# Sch.net
KiCad netlist of a schematic drawn in Altium Designer
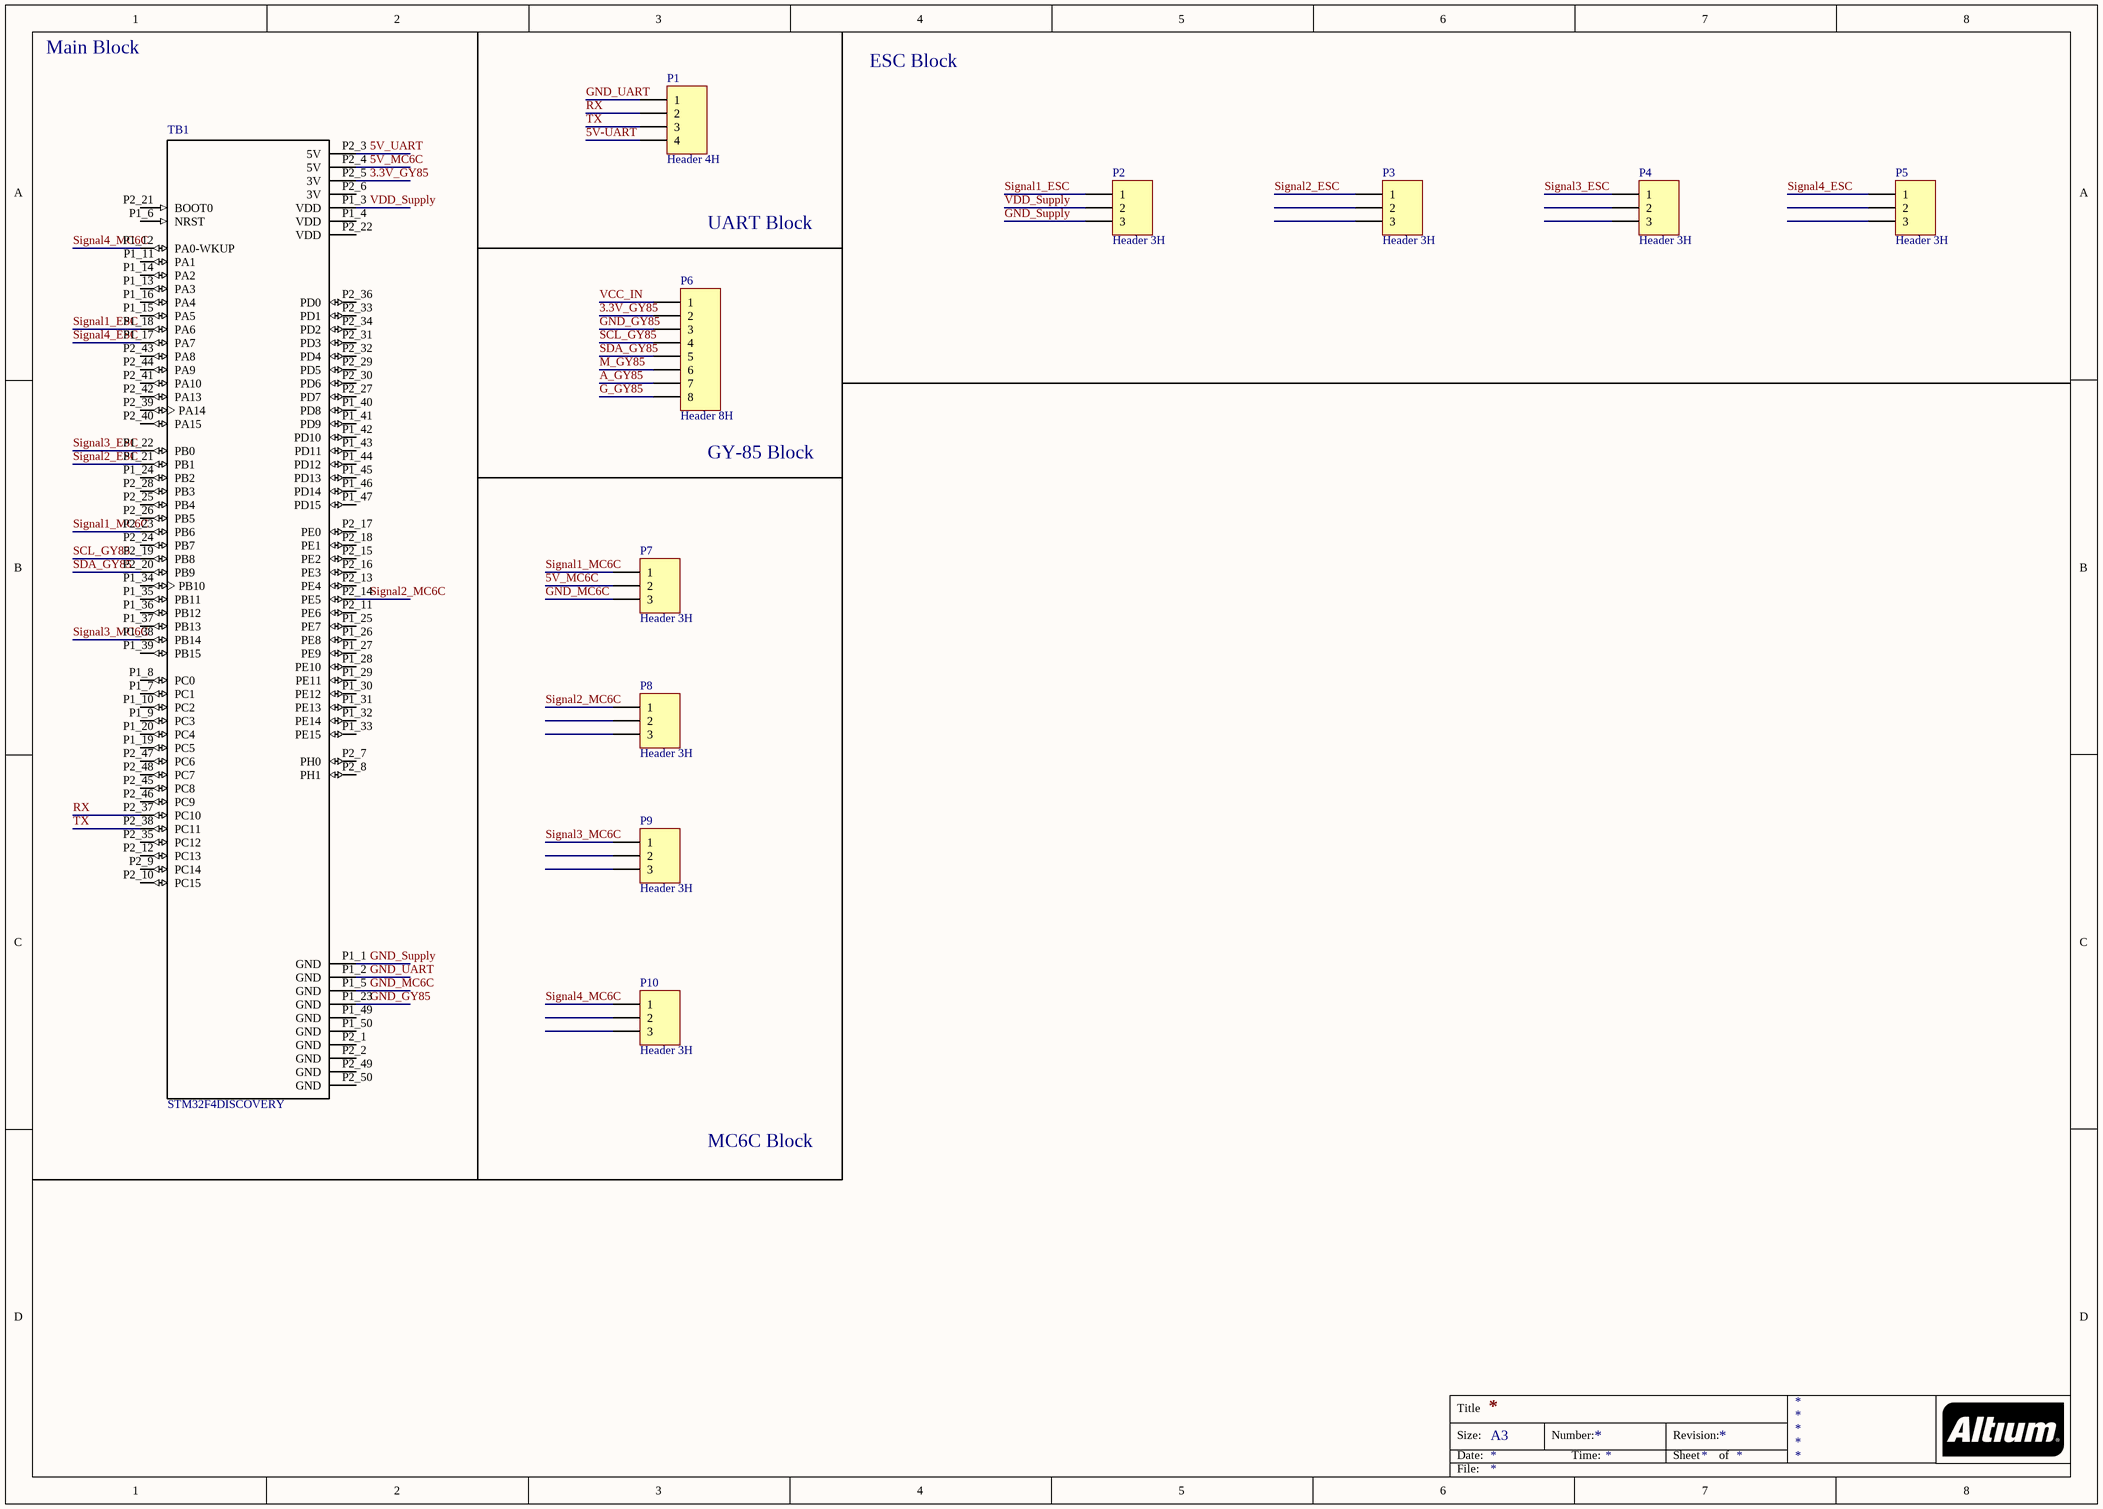
[diagram p0: Sch.SchDoc]

(export (version "E")
  (design (tool "Eeschema 10.0.6"))
  (components
    (comp (ref "P1")
      (value "Header 4H")
      (footprint "HDR1X4H")
      (description "Header, 4-Pin, Right Angle")
      (fields (field (name "PUBLISHER") "Altium Limited"))
      (libsource (lib "Miscellaneous Connectors") (part "Header 4H"))
    )
    (comp (ref "P2")
      (value "Header 3H")
      (footprint "HDR1X3H")
      (description "Header, 3-Pin, Right Angle")
      (fields (field (name "PUBLISHER") "Altium Limited"))
      (libsource (lib "Miscellaneous Connectors") (part "Header 3H"))
    )
    (comp (ref "P3")
      (value "Header 3H")
      (footprint "HDR1X3H")
      (description "Header, 3-Pin, Right Angle")
      (fields (field (name "PUBLISHER") "Altium Limited"))
      (libsource (lib "Miscellaneous Connectors") (part "Header 3H"))
    )
    (comp (ref "P4")
      (value "Header 3H")
      (footprint "HDR1X3H")
      (description "Header, 3-Pin, Right Angle")
      (fields (field (name "PUBLISHER") "Altium Limited"))
      (libsource (lib "Miscellaneous Connectors") (part "Header 3H"))
    )
    (comp (ref "P5")
      (value "Header 3H")
      (footprint "HDR1X3H")
      (description "Header, 3-Pin, Right Angle")
      (fields (field (name "PUBLISHER") "Altium Limited"))
      (libsource (lib "Miscellaneous Connectors") (part "Header 3H"))
    )
    (comp (ref "P6")
      (value "Header 8H")
      (footprint "HDR1X8H")
      (description "Header, 8-Pin, Right Angle")
      (fields (field (name "PUBLISHER") "Altium Limited"))
      (libsource (lib "Miscellaneous Connectors") (part "Header 8H"))
    )
    (comp (ref "P7")
      (value "Header 3H")
      (footprint "HDR1X3H")
      (description "Header, 3-Pin, Right Angle")
      (fields (field (name "PUBLISHER") "Altium Limited"))
      (libsource (lib "Miscellaneous Connectors") (part "Header 3H"))
    )
    (comp (ref "P8")
      (value "Header 3H")
      (footprint "HDR1X3H")
      (description "Header, 3-Pin, Right Angle")
      (fields (field (name "PUBLISHER") "Altium Limited"))
      (libsource (lib "Miscellaneous Connectors") (part "Header 3H"))
    )
    (comp (ref "P9")
      (value "Header 3H")
      (footprint "HDR1X3H")
      (description "Header, 3-Pin, Right Angle")
      (fields (field (name "PUBLISHER") "Altium Limited"))
      (libsource (lib "Miscellaneous Connectors") (part "Header 3H"))
    )
    (comp (ref "P10")
      (value "Header 3H")
      (footprint "HDR1X3H")
      (description "Header, 3-Pin, Right Angle")
      (fields (field (name "PUBLISHER") "Altium Limited"))
      (libsource (lib "Miscellaneous Connectors") (part "Header 3H"))
    )
    (comp (ref "TB1")
      (value "STM32F4DISCOVERY")
      (footprint "*MODULE_STM32F4DISCOVERY_STM32F4DISCOVERY(Primary)")
      (description "STM32F407VGT6 Discovery STM32F4 ARMÂ® CortexÂ®-M4 MCU 32-Bit Embedded Evaluation Board")
      (fields (field (name "MF") "STMicroelectronics"))
      (libsource (lib "STM32F4DISCOVERY") (part "STM32F4DISCOVERY"))
    )
  )
  (nets
    (net (code "1") (name "/3.3V_GY85") (class "Default")
      (node (ref "P6") (pin "2") (pinfunction "2_2") (pintype "passive"))
      (node (ref "TB1") (pin "P2_5") (pinfunction "3V_P2_5") (pintype "power_in"))
    )
    (net (code "2") (name "/5V-UART") (class "Default")
      (node (ref "P1") (pin "4") (pinfunction "4_4") (pintype "passive"))
    )
    (net (code "3") (name "/5V_MC6C") (class "Default")
      (node (ref "P7") (pin "2") (pinfunction "2_2") (pintype "passive"))
      (node (ref "TB1") (pin "P2_4") (pinfunction "5V_P2_4") (pintype "power_in"))
    )
    (net (code "4") (name "/5V_UART") (class "Default")
      (node (ref "TB1") (pin "P2_3") (pinfunction "5V_P2_3") (pintype "power_in"))
    )
    (net (code "5") (name "/A_GY85") (class "Default")
      (node (ref "P6") (pin "7") (pinfunction "7_7") (pintype "passive"))
    )
    (net (code "6") (name "/GND_GY85") (class "Default")
      (node (ref "P6") (pin "3") (pinfunction "3_3") (pintype "passive"))
      (node (ref "TB1") (pin "P1_23") (pinfunction "GND_P1_23") (pintype "power_in"))
    )
    (net (code "7") (name "/GND_MC6C") (class "Default")
      (node (ref "P7") (pin "3") (pinfunction "3_3") (pintype "passive"))
      (node (ref "TB1") (pin "P1_5") (pinfunction "GND_P1_5") (pintype "power_in"))
    )
    (net (code "8") (name "/GND_Supply") (class "Default")
      (node (ref "P2") (pin "3") (pinfunction "3_3") (pintype "passive"))
      (node (ref "TB1") (pin "P1_1") (pinfunction "GND_P1_1") (pintype "power_in"))
    )
    (net (code "9") (name "/GND_UART") (class "Default")
      (node (ref "P1") (pin "1") (pinfunction "1_1") (pintype "passive"))
      (node (ref "TB1") (pin "P1_2") (pinfunction "GND_P1_2") (pintype "power_in"))
    )
    (net (code "10") (name "/G_GY85") (class "Default")
      (node (ref "P6") (pin "8") (pinfunction "8_8") (pintype "passive"))
    )
    (net (code "11") (name "/M_GY85") (class "Default")
      (node (ref "P6") (pin "6") (pinfunction "6_6") (pintype "passive"))
    )
    (net (code "12") (name "/RX") (class "Default")
      (node (ref "P1") (pin "2") (pinfunction "2_2") (pintype "passive"))
      (node (ref "TB1") (pin "P2_37") (pinfunction "PC10_P2_37") (pintype "bidirectional"))
    )
    (net (code "13") (name "/SCL_GY85") (class "Default")
      (node (ref "P6") (pin "4") (pinfunction "4_4") (pintype "passive"))
      (node (ref "TB1") (pin "P2_19") (pinfunction "PB8_P2_19") (pintype "bidirectional"))
    )
    (net (code "14") (name "/SDA_GY85") (class "Default")
      (node (ref "P6") (pin "5") (pinfunction "5_5") (pintype "passive"))
      (node (ref "TB1") (pin "P2_20") (pinfunction "PB9_P2_20") (pintype "bidirectional"))
    )
    (net (code "15") (name "/Signal1_ESC") (class "Default")
      (node (ref "P2") (pin "1") (pinfunction "1_1") (pintype "passive"))
      (node (ref "TB1") (pin "P1_18") (pinfunction "PA6_P1_18") (pintype "bidirectional"))
    )
    (net (code "16") (name "/Signal1_MC6C") (class "Default")
      (node (ref "P7") (pin "1") (pinfunction "1_1") (pintype "passive"))
      (node (ref "TB1") (pin "P2_23") (pinfunction "PB6_P2_23") (pintype "bidirectional"))
    )
    (net (code "17") (name "/Signal2_ESC") (class "Default")
      (node (ref "P3") (pin "1") (pinfunction "1_1") (pintype "passive"))
      (node (ref "TB1") (pin "P1_21") (pinfunction "PB1_P1_21") (pintype "bidirectional"))
    )
    (net (code "18") (name "/Signal2_MC6C") (class "Default")
      (node (ref "P8") (pin "1") (pinfunction "1_1") (pintype "passive"))
      (node (ref "TB1") (pin "P2_14") (pinfunction "PE5_P2_14") (pintype "bidirectional"))
    )
    (net (code "19") (name "/Signal3_ESC") (class "Default")
      (node (ref "P4") (pin "1") (pinfunction "1_1") (pintype "passive"))
      (node (ref "TB1") (pin "P1_22") (pinfunction "PB0_P1_22") (pintype "bidirectional"))
    )
    (net (code "20") (name "/Signal3_MC6C") (class "Default")
      (node (ref "P9") (pin "1") (pinfunction "1_1") (pintype "passive"))
      (node (ref "TB1") (pin "P1_38") (pinfunction "PB14_P1_38") (pintype "bidirectional"))
    )
    (net (code "21") (name "/Signal4_ESC") (class "Default")
      (node (ref "P5") (pin "1") (pinfunction "1_1") (pintype "passive"))
      (node (ref "TB1") (pin "P1_17") (pinfunction "PA7_P1_17") (pintype "bidirectional"))
    )
    (net (code "22") (name "/Signal4_MC6C") (class "Default")
      (node (ref "P10") (pin "1") (pinfunction "1_1") (pintype "passive"))
      (node (ref "TB1") (pin "P1_12") (pinfunction "PA0-WKUP_P1_12") (pintype "bidirectional"))
    )
    (net (code "23") (name "/TX") (class "Default")
      (node (ref "P1") (pin "3") (pinfunction "3_3") (pintype "passive"))
      (node (ref "TB1") (pin "P2_38") (pinfunction "PC11_P2_38") (pintype "bidirectional"))
    )
    (net (code "24") (name "/VCC_IN") (class "Default")
      (node (ref "P6") (pin "1") (pinfunction "1_1") (pintype "passive"))
    )
    (net (code "25") (name "/VDD_Supply") (class "Default")
      (node (ref "P2") (pin "2") (pinfunction "2_2") (pintype "passive"))
      (node (ref "TB1") (pin "P1_3") (pinfunction "VDD_P1_3") (pintype "power_in"))
    )
    (net (code "26") (name "unconnected-(P3-Pad2)") (class "Default")
      (node (ref "P3") (pin "2") (pinfunction "2_2") (pintype "passive"))
    )
    (net (code "27") (name "unconnected-(P3-Pad3)") (class "Default")
      (node (ref "P3") (pin "3") (pinfunction "3_3") (pintype "passive"))
    )
    (net (code "28") (name "unconnected-(P4-Pad2)") (class "Default")
      (node (ref "P4") (pin "2") (pinfunction "2_2") (pintype "passive"))
    )
    (net (code "29") (name "unconnected-(P4-Pad3)") (class "Default")
      (node (ref "P4") (pin "3") (pinfunction "3_3") (pintype "passive"))
    )
    (net (code "30") (name "unconnected-(P5-Pad2)") (class "Default")
      (node (ref "P5") (pin "2") (pinfunction "2_2") (pintype "passive"))
    )
    (net (code "31") (name "unconnected-(P5-Pad3)") (class "Default")
      (node (ref "P5") (pin "3") (pinfunction "3_3") (pintype "passive"))
    )
    (net (code "32") (name "unconnected-(P8-Pad2)") (class "Default")
      (node (ref "P8") (pin "2") (pinfunction "2_2") (pintype "passive"))
    )
    (net (code "33") (name "unconnected-(P8-Pad3)") (class "Default")
      (node (ref "P8") (pin "3") (pinfunction "3_3") (pintype "passive"))
    )
    (net (code "34") (name "unconnected-(P9-Pad2)") (class "Default")
      (node (ref "P9") (pin "2") (pinfunction "2_2") (pintype "passive"))
    )
    (net (code "35") (name "unconnected-(P9-Pad3)") (class "Default")
      (node (ref "P9") (pin "3") (pinfunction "3_3") (pintype "passive"))
    )
    (net (code "36") (name "unconnected-(P10-Pad2)") (class "Default")
      (node (ref "P10") (pin "2") (pinfunction "2_2") (pintype "passive"))
    )
    (net (code "37") (name "unconnected-(P10-Pad3)") (class "Default")
      (node (ref "P10") (pin "3") (pinfunction "3_3") (pintype "passive"))
    )
    (net (code "38") (name "unconnected-(TB1-3V-PadP2_6)") (class "Default")
      (node (ref "TB1") (pin "P2_6") (pinfunction "3V_P2_6") (pintype "power_in"))
    )
    (net (code "39") (name "unconnected-(TB1-BOOT0-PadP2_21)") (class "Default")
      (node (ref "TB1") (pin "P2_21") (pinfunction "BOOT0_P2_21") (pintype "input"))
    )
    (net (code "40") (name "unconnected-(TB1-GND-PadP1_49)") (class "Default")
      (node (ref "TB1") (pin "P1_49") (pinfunction "GND_P1_49") (pintype "power_in"))
    )
    (net (code "41") (name "unconnected-(TB1-GND-PadP1_50)") (class "Default")
      (node (ref "TB1") (pin "P1_50") (pinfunction "GND_P1_50") (pintype "power_in"))
    )
    (net (code "42") (name "unconnected-(TB1-GND-PadP2_1)") (class "Default")
      (node (ref "TB1") (pin "P2_1") (pinfunction "GND_P2_1") (pintype "power_in"))
    )
    (net (code "43") (name "unconnected-(TB1-GND-PadP2_2)") (class "Default")
      (node (ref "TB1") (pin "P2_2") (pinfunction "GND_P2_2") (pintype "power_in"))
    )
    (net (code "44") (name "unconnected-(TB1-GND-PadP2_49)") (class "Default")
      (node (ref "TB1") (pin "P2_49") (pinfunction "GND_P2_49") (pintype "power_in"))
    )
    (net (code "45") (name "unconnected-(TB1-GND-PadP2_50)") (class "Default")
      (node (ref "TB1") (pin "P2_50") (pinfunction "GND_P2_50") (pintype "power_in"))
    )
    (net (code "46") (name "unconnected-(TB1-NRST-PadP1_6)") (class "Default")
      (node (ref "TB1") (pin "P1_6") (pinfunction "NRST_P1_6") (pintype "input"))
    )
    (net (code "47") (name "unconnected-(TB1-PA1-PadP1_11)") (class "Default")
      (node (ref "TB1") (pin "P1_11") (pinfunction "PA1_P1_11") (pintype "bidirectional"))
    )
    (net (code "48") (name "unconnected-(TB1-PA2-PadP1_14)") (class "Default")
      (node (ref "TB1") (pin "P1_14") (pinfunction "PA2_P1_14") (pintype "bidirectional"))
    )
    (net (code "49") (name "unconnected-(TB1-PA3-PadP1_13)") (class "Default")
      (node (ref "TB1") (pin "P1_13") (pinfunction "PA3_P1_13") (pintype "bidirectional"))
    )
    (net (code "50") (name "unconnected-(TB1-PA4-PadP1_16)") (class "Default")
      (node (ref "TB1") (pin "P1_16") (pinfunction "PA4_P1_16") (pintype "bidirectional"))
    )
    (net (code "51") (name "unconnected-(TB1-PA5-PadP1_15)") (class "Default")
      (node (ref "TB1") (pin "P1_15") (pinfunction "PA5_P1_15") (pintype "bidirectional"))
    )
    (net (code "52") (name "unconnected-(TB1-PA8-PadP2_43)") (class "Default")
      (node (ref "TB1") (pin "P2_43") (pinfunction "PA8_P2_43") (pintype "bidirectional"))
    )
    (net (code "53") (name "unconnected-(TB1-PA9-PadP2_44)") (class "Default")
      (node (ref "TB1") (pin "P2_44") (pinfunction "PA9_P2_44") (pintype "bidirectional"))
    )
    (net (code "54") (name "unconnected-(TB1-PA10-PadP2_41)") (class "Default")
      (node (ref "TB1") (pin "P2_41") (pinfunction "PA10_P2_41") (pintype "bidirectional"))
    )
    (net (code "55") (name "unconnected-(TB1-PA13-PadP2_42)") (class "Default")
      (node (ref "TB1") (pin "P2_42") (pinfunction "PA13_P2_42") (pintype "bidirectional"))
    )
    (net (code "56") (name "unconnected-(TB1-PA14-PadP2_39)") (class "Default")
      (node (ref "TB1") (pin "P2_39") (pinfunction "PA14_P2_39") (pintype "bidirectional"))
    )
    (net (code "57") (name "unconnected-(TB1-PA15-PadP2_40)") (class "Default")
      (node (ref "TB1") (pin "P2_40") (pinfunction "PA15_P2_40") (pintype "bidirectional"))
    )
    (net (code "58") (name "unconnected-(TB1-PB2-PadP1_24)") (class "Default")
      (node (ref "TB1") (pin "P1_24") (pinfunction "PB2_P1_24") (pintype "bidirectional"))
    )
    (net (code "59") (name "unconnected-(TB1-PB3-PadP2_28)") (class "Default")
      (node (ref "TB1") (pin "P2_28") (pinfunction "PB3_P2_28") (pintype "bidirectional"))
    )
    (net (code "60") (name "unconnected-(TB1-PB4-PadP2_25)") (class "Default")
      (node (ref "TB1") (pin "P2_25") (pinfunction "PB4_P2_25") (pintype "bidirectional"))
    )
    (net (code "61") (name "unconnected-(TB1-PB5-PadP2_26)") (class "Default")
      (node (ref "TB1") (pin "P2_26") (pinfunction "PB5_P2_26") (pintype "bidirectional"))
    )
    (net (code "62") (name "unconnected-(TB1-PB7-PadP2_24)") (class "Default")
      (node (ref "TB1") (pin "P2_24") (pinfunction "PB7_P2_24") (pintype "bidirectional"))
    )
    (net (code "63") (name "unconnected-(TB1-PB10-PadP1_34)") (class "Default")
      (node (ref "TB1") (pin "P1_34") (pinfunction "PB10_P1_34") (pintype "bidirectional"))
    )
    (net (code "64") (name "unconnected-(TB1-PB11-PadP1_35)") (class "Default")
      (node (ref "TB1") (pin "P1_35") (pinfunction "PB11_P1_35") (pintype "bidirectional"))
    )
    (net (code "65") (name "unconnected-(TB1-PB12-PadP1_36)") (class "Default")
      (node (ref "TB1") (pin "P1_36") (pinfunction "PB12_P1_36") (pintype "bidirectional"))
    )
    (net (code "66") (name "unconnected-(TB1-PB13-PadP1_37)") (class "Default")
      (node (ref "TB1") (pin "P1_37") (pinfunction "PB13_P1_37") (pintype "bidirectional"))
    )
    (net (code "67") (name "unconnected-(TB1-PB15-PadP1_39)") (class "Default")
      (node (ref "TB1") (pin "P1_39") (pinfunction "PB15_P1_39") (pintype "bidirectional"))
    )
    (net (code "68") (name "unconnected-(TB1-PC0-PadP1_8)") (class "Default")
      (node (ref "TB1") (pin "P1_8") (pinfunction "PC0_P1_8") (pintype "bidirectional"))
    )
    (net (code "69") (name "unconnected-(TB1-PC1-PadP1_7)") (class "Default")
      (node (ref "TB1") (pin "P1_7") (pinfunction "PC1_P1_7") (pintype "bidirectional"))
    )
    (net (code "70") (name "unconnected-(TB1-PC2-PadP1_10)") (class "Default")
      (node (ref "TB1") (pin "P1_10") (pinfunction "PC2_P1_10") (pintype "bidirectional"))
    )
    (net (code "71") (name "unconnected-(TB1-PC3-PadP1_9)") (class "Default")
      (node (ref "TB1") (pin "P1_9") (pinfunction "PC3_P1_9") (pintype "bidirectional"))
    )
    (net (code "72") (name "unconnected-(TB1-PC4-PadP1_20)") (class "Default")
      (node (ref "TB1") (pin "P1_20") (pinfunction "PC4_P1_20") (pintype "bidirectional"))
    )
    (net (code "73") (name "unconnected-(TB1-PC5-PadP1_19)") (class "Default")
      (node (ref "TB1") (pin "P1_19") (pinfunction "PC5_P1_19") (pintype "bidirectional"))
    )
    (net (code "74") (name "unconnected-(TB1-PC6-PadP2_47)") (class "Default")
      (node (ref "TB1") (pin "P2_47") (pinfunction "PC6_P2_47") (pintype "bidirectional"))
    )
    (net (code "75") (name "unconnected-(TB1-PC7-PadP2_48)") (class "Default")
      (node (ref "TB1") (pin "P2_48") (pinfunction "PC7_P2_48") (pintype "bidirectional"))
    )
    (net (code "76") (name "unconnected-(TB1-PC8-PadP2_45)") (class "Default")
      (node (ref "TB1") (pin "P2_45") (pinfunction "PC8_P2_45") (pintype "bidirectional"))
    )
    (net (code "77") (name "unconnected-(TB1-PC9-PadP2_46)") (class "Default")
      (node (ref "TB1") (pin "P2_46") (pinfunction "PC9_P2_46") (pintype "bidirectional"))
    )
    (net (code "78") (name "unconnected-(TB1-PC12-PadP2_35)") (class "Default")
      (node (ref "TB1") (pin "P2_35") (pinfunction "PC12_P2_35") (pintype "bidirectional"))
    )
    (net (code "79") (name "unconnected-(TB1-PC13-PadP2_12)") (class "Default")
      (node (ref "TB1") (pin "P2_12") (pinfunction "PC13_P2_12") (pintype "bidirectional"))
    )
    (net (code "80") (name "unconnected-(TB1-PC14-PadP2_9)") (class "Default")
      (node (ref "TB1") (pin "P2_9") (pinfunction "PC14_P2_9") (pintype "bidirectional"))
    )
    (net (code "81") (name "unconnected-(TB1-PC15-PadP2_10)") (class "Default")
      (node (ref "TB1") (pin "P2_10") (pinfunction "PC15_P2_10") (pintype "bidirectional"))
    )
    (net (code "82") (name "unconnected-(TB1-PD0-PadP2_36)") (class "Default")
      (node (ref "TB1") (pin "P2_36") (pinfunction "PD0_P2_36") (pintype "bidirectional"))
    )
    (net (code "83") (name "unconnected-(TB1-PD1-PadP2_33)") (class "Default")
      (node (ref "TB1") (pin "P2_33") (pinfunction "PD1_P2_33") (pintype "bidirectional"))
    )
    (net (code "84") (name "unconnected-(TB1-PD2-PadP2_34)") (class "Default")
      (node (ref "TB1") (pin "P2_34") (pinfunction "PD2_P2_34") (pintype "bidirectional"))
    )
    (net (code "85") (name "unconnected-(TB1-PD3-PadP2_31)") (class "Default")
      (node (ref "TB1") (pin "P2_31") (pinfunction "PD3_P2_31") (pintype "bidirectional"))
    )
    (net (code "86") (name "unconnected-(TB1-PD4-PadP2_32)") (class "Default")
      (node (ref "TB1") (pin "P2_32") (pinfunction "PD4_P2_32") (pintype "bidirectional"))
    )
    (net (code "87") (name "unconnected-(TB1-PD5-PadP2_29)") (class "Default")
      (node (ref "TB1") (pin "P2_29") (pinfunction "PD5_P2_29") (pintype "bidirectional"))
    )
    (net (code "88") (name "unconnected-(TB1-PD6-PadP2_30)") (class "Default")
      (node (ref "TB1") (pin "P2_30") (pinfunction "PD6_P2_30") (pintype "bidirectional"))
    )
    (net (code "89") (name "unconnected-(TB1-PD7-PadP2_27)") (class "Default")
      (node (ref "TB1") (pin "P2_27") (pinfunction "PD7_P2_27") (pintype "bidirectional"))
    )
    (net (code "90") (name "unconnected-(TB1-PD8-PadP1_40)") (class "Default")
      (node (ref "TB1") (pin "P1_40") (pinfunction "PD8_P1_40") (pintype "bidirectional"))
    )
    (net (code "91") (name "unconnected-(TB1-PD9-PadP1_41)") (class "Default")
      (node (ref "TB1") (pin "P1_41") (pinfunction "PD9_P1_41") (pintype "bidirectional"))
    )
    (net (code "92") (name "unconnected-(TB1-PD10-PadP1_42)") (class "Default")
      (node (ref "TB1") (pin "P1_42") (pinfunction "PD10_P1_42") (pintype "bidirectional"))
    )
    (net (code "93") (name "unconnected-(TB1-PD11-PadP1_43)") (class "Default")
      (node (ref "TB1") (pin "P1_43") (pinfunction "PD11_P1_43") (pintype "bidirectional"))
    )
    (net (code "94") (name "unconnected-(TB1-PD12-PadP1_44)") (class "Default")
      (node (ref "TB1") (pin "P1_44") (pinfunction "PD12_P1_44") (pintype "bidirectional"))
    )
    (net (code "95") (name "unconnected-(TB1-PD13-PadP1_45)") (class "Default")
      (node (ref "TB1") (pin "P1_45") (pinfunction "PD13_P1_45") (pintype "bidirectional"))
    )
    (net (code "96") (name "unconnected-(TB1-PD14-PadP1_46)") (class "Default")
      (node (ref "TB1") (pin "P1_46") (pinfunction "PD14_P1_46") (pintype "bidirectional"))
    )
    (net (code "97") (name "unconnected-(TB1-PD15-PadP1_47)") (class "Default")
      (node (ref "TB1") (pin "P1_47") (pinfunction "PD15_P1_47") (pintype "bidirectional"))
    )
    (net (code "98") (name "unconnected-(TB1-PE0-PadP2_17)") (class "Default")
      (node (ref "TB1") (pin "P2_17") (pinfunction "PE0_P2_17") (pintype "bidirectional"))
    )
    (net (code "99") (name "unconnected-(TB1-PE1-PadP2_18)") (class "Default")
      (node (ref "TB1") (pin "P2_18") (pinfunction "PE1_P2_18") (pintype "bidirectional"))
    )
    (net (code "100") (name "unconnected-(TB1-PE2-PadP2_15)") (class "Default")
      (node (ref "TB1") (pin "P2_15") (pinfunction "PE2_P2_15") (pintype "bidirectional"))
    )
    (net (code "101") (name "unconnected-(TB1-PE3-PadP2_16)") (class "Default")
      (node (ref "TB1") (pin "P2_16") (pinfunction "PE3_P2_16") (pintype "bidirectional"))
    )
    (net (code "102") (name "unconnected-(TB1-PE4-PadP2_13)") (class "Default")
      (node (ref "TB1") (pin "P2_13") (pinfunction "PE4_P2_13") (pintype "bidirectional"))
    )
    (net (code "103") (name "unconnected-(TB1-PE6-PadP2_11)") (class "Default")
      (node (ref "TB1") (pin "P2_11") (pinfunction "PE6_P2_11") (pintype "bidirectional"))
    )
    (net (code "104") (name "unconnected-(TB1-PE7-PadP1_25)") (class "Default")
      (node (ref "TB1") (pin "P1_25") (pinfunction "PE7_P1_25") (pintype "bidirectional"))
    )
    (net (code "105") (name "unconnected-(TB1-PE8-PadP1_26)") (class "Default")
      (node (ref "TB1") (pin "P1_26") (pinfunction "PE8_P1_26") (pintype "bidirectional"))
    )
    (net (code "106") (name "unconnected-(TB1-PE9-PadP1_27)") (class "Default")
      (node (ref "TB1") (pin "P1_27") (pinfunction "PE9_P1_27") (pintype "bidirectional"))
    )
    (net (code "107") (name "unconnected-(TB1-PE10-PadP1_28)") (class "Default")
      (node (ref "TB1") (pin "P1_28") (pinfunction "PE10_P1_28") (pintype "bidirectional"))
    )
    (net (code "108") (name "unconnected-(TB1-PE11-PadP1_29)") (class "Default")
      (node (ref "TB1") (pin "P1_29") (pinfunction "PE11_P1_29") (pintype "bidirectional"))
    )
    (net (code "109") (name "unconnected-(TB1-PE12-PadP1_30)") (class "Default")
      (node (ref "TB1") (pin "P1_30") (pinfunction "PE12_P1_30") (pintype "bidirectional"))
    )
    (net (code "110") (name "unconnected-(TB1-PE13-PadP1_31)") (class "Default")
      (node (ref "TB1") (pin "P1_31") (pinfunction "PE13_P1_31") (pintype "bidirectional"))
    )
    (net (code "111") (name "unconnected-(TB1-PE14-PadP1_32)") (class "Default")
      (node (ref "TB1") (pin "P1_32") (pinfunction "PE14_P1_32") (pintype "bidirectional"))
    )
    (net (code "112") (name "unconnected-(TB1-PE15-PadP1_33)") (class "Default")
      (node (ref "TB1") (pin "P1_33") (pinfunction "PE15_P1_33") (pintype "bidirectional"))
    )
    (net (code "113") (name "unconnected-(TB1-PH0-PadP2_7)") (class "Default")
      (node (ref "TB1") (pin "P2_7") (pinfunction "PH0_P2_7") (pintype "bidirectional"))
    )
    (net (code "114") (name "unconnected-(TB1-PH1-PadP2_8)") (class "Default")
      (node (ref "TB1") (pin "P2_8") (pinfunction "PH1_P2_8") (pintype "bidirectional"))
    )
    (net (code "115") (name "unconnected-(TB1-VDD-PadP1_4)") (class "Default")
      (node (ref "TB1") (pin "P1_4") (pinfunction "VDD_P1_4") (pintype "power_in"))
    )
    (net (code "116") (name "unconnected-(TB1-VDD-PadP2_22)") (class "Default")
      (node (ref "TB1") (pin "P2_22") (pinfunction "VDD_P2_22") (pintype "power_in"))
    )
  )
)
